# MUX.net
KiCad netlist of a schematic drawn in Altium Designer
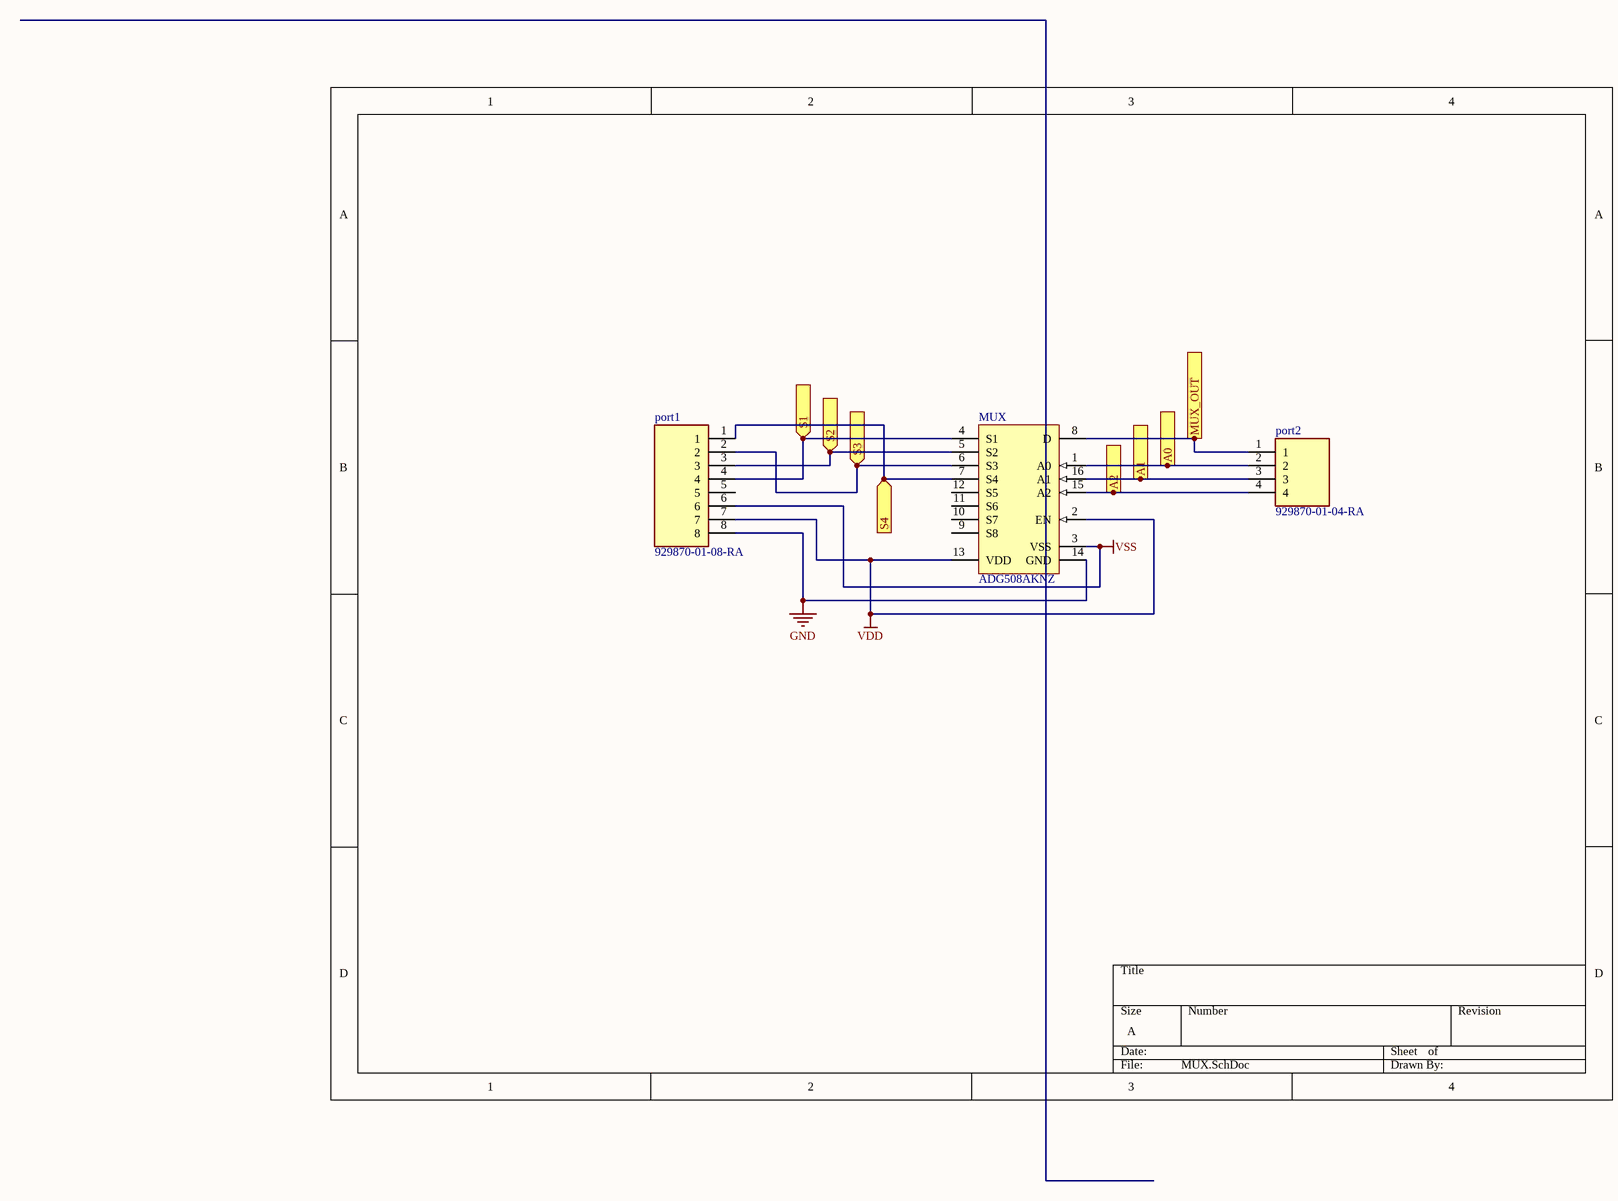
[diagram p0: MUX.SchDoc]

(export (version "E")
  (design (tool "Eeschema 10.0.6"))
  (components
    (comp (ref "MUX")
      (value "ADG508AKNZ")
      (footprint "ADI-N-16")
      (description "CMOS 8-Channel Analog Multiplexer, 280 Ohm / 500 Ohm Ron, 16-pin DIP (N-16), Tube")
      (fields (field (name "MANUFACTURER") "Analog Devices"))
      (libsource (lib "Altium Content Vault") (part "ADI-ADG508A-N-16"))
    )
    (comp (ref "port1")
      (value "929870-01-08-RA")
      (footprint "SamacSys:RHDR8W64P0X254_1X8_2032X254X380P")
      (description "Connector")
      (fields (field (name "MOUSER PART NUMBER") "517-929870-01-08-RA"))
      (libsource (lib "*") (part "929870-01-08-RA"))
    )
    (comp (ref "port2")
      (value "929870-01-04-RA")
      (footprint "SamacSys:RHDR4W76P0X254_1X4_1016X254X826P")
      (description "Connector")
      (fields (field (name "MOUSER PART NUMBER") "517-929870-01-04-RA"))
      (libsource (lib "*") (part "929870-01-04-RA"))
    )
  )
  (nets
    (net (code "1") (name "/A0") (class "Default")
      (node (ref "MUX") (pin "1") (pinfunction "A0_1") (pintype "input"))
      (node (ref "port2") (pin "2") (pinfunction "2_2") (pintype "passive"))
    )
    (net (code "2") (name "/A1") (class "Default")
      (node (ref "MUX") (pin "16") (pinfunction "A1_16") (pintype "input"))
      (node (ref "port2") (pin "3") (pinfunction "3_3") (pintype "passive"))
    )
    (net (code "3") (name "/A2") (class "Default")
      (node (ref "MUX") (pin "15") (pinfunction "A2_15") (pintype "input"))
      (node (ref "port2") (pin "4") (pinfunction "4_4") (pintype "passive"))
    )
    (net (code "4") (name "/MUX_OUT") (class "Default")
      (node (ref "MUX") (pin "8") (pinfunction "D_8") (pintype "passive"))
      (node (ref "port2") (pin "1") (pinfunction "1_1") (pintype "passive"))
    )
    (net (code "5") (name "/S1") (class "Default")
      (node (ref "MUX") (pin "4") (pinfunction "S1_4") (pintype "passive"))
      (node (ref "port1") (pin "4") (pinfunction "4_4") (pintype "passive"))
    )
    (net (code "6") (name "/S2") (class "Default")
      (node (ref "MUX") (pin "5") (pinfunction "S2_5") (pintype "passive"))
      (node (ref "port1") (pin "3") (pinfunction "3_3") (pintype "passive"))
    )
    (net (code "7") (name "/S3") (class "Default")
      (node (ref "MUX") (pin "6") (pinfunction "S3_6") (pintype "passive"))
      (node (ref "port1") (pin "2") (pinfunction "2_2") (pintype "passive"))
    )
    (net (code "8") (name "/S4") (class "Default")
      (node (ref "MUX") (pin "7") (pinfunction "S4_7") (pintype "passive"))
      (node (ref "port1") (pin "1") (pinfunction "1_1") (pintype "passive"))
    )
    (net (code "9") (name "GND") (class "Default")
      (node (ref "MUX") (pin "14") (pinfunction "GND_14") (pintype "power_in"))
      (node (ref "port1") (pin "8") (pinfunction "8_8") (pintype "passive"))
    )
    (net (code "10") (name "VDD") (class "Default")
      (node (ref "MUX") (pin "13") (pinfunction "VDD_13") (pintype "power_in"))
      (node (ref "MUX") (pin "2") (pinfunction "EN_2") (pintype "input"))
      (node (ref "port1") (pin "7") (pinfunction "7_7") (pintype "passive"))
    )
    (net (code "11") (name "VSS") (class "Default")
      (node (ref "MUX") (pin "3") (pinfunction "VSS_3") (pintype "power_in"))
      (node (ref "port1") (pin "6") (pinfunction "6_6") (pintype "passive"))
    )
    (net (code "12") (name "unconnected-(MUX-S5-Pad12)") (class "Default")
      (node (ref "MUX") (pin "12") (pinfunction "S5_12") (pintype "passive"))
    )
    (net (code "13") (name "unconnected-(MUX-S6-Pad11)") (class "Default")
      (node (ref "MUX") (pin "11") (pinfunction "S6_11") (pintype "passive"))
    )
    (net (code "14") (name "unconnected-(MUX-S7-Pad10)") (class "Default")
      (node (ref "MUX") (pin "10") (pinfunction "S7_10") (pintype "passive"))
    )
    (net (code "15") (name "unconnected-(MUX-S8-Pad9)") (class "Default")
      (node (ref "MUX") (pin "9") (pinfunction "S8_9") (pintype "passive"))
    )
    (net (code "16") (name "unconnected-(port1-Pad5)") (class "Default")
      (node (ref "port1") (pin "5") (pinfunction "5_5") (pintype "passive"))
    )
  )
)
